# Shibobi_PowerMeasure.net
KiCad netlist of a schematic drawn in EAGLE
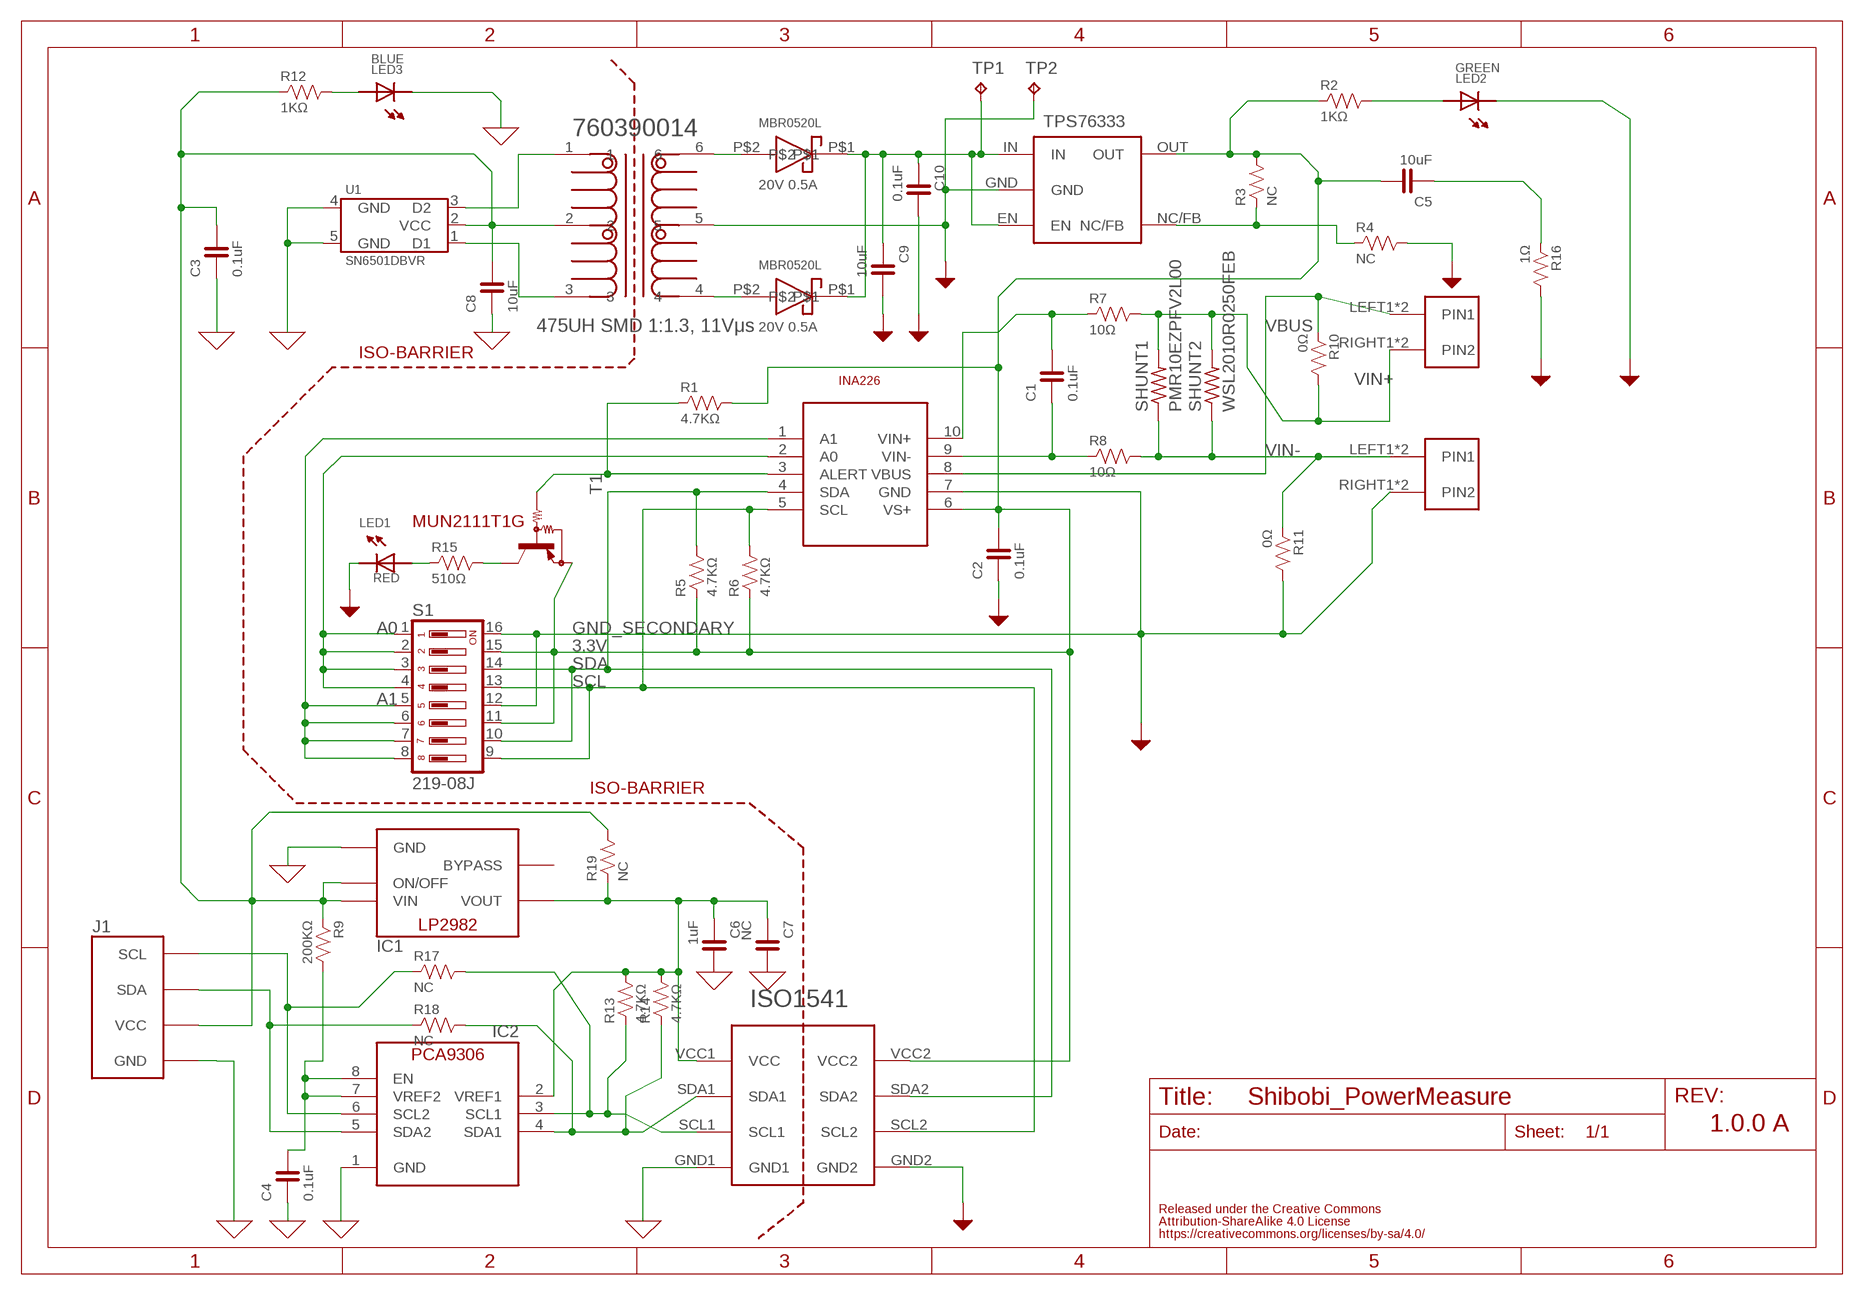
[diagram p0: schematic, sheet 1]

(export (version "E")
  (design (tool "Eeschema 10.0.6"))
  (components
    (comp (ref "C1")
      (value "0.1uF")
      (footprint "eagle-import:0603")
      (libsource (lib "eagle-import") (part "CAPACITOR-0603"))
    )
    (comp (ref "C2")
      (value "0.1uF")
      (footprint "eagle-import:0603")
      (libsource (lib "eagle-import") (part "CAPACITOR-0603"))
    )
    (comp (ref "C3")
      (value "0.1uF")
      (footprint "eagle-import:0603")
      (libsource (lib "eagle-import") (part "CAPACITOR-0603"))
    )
    (comp (ref "C4")
      (value "0.1uF")
      (footprint "eagle-import:0603")
      (libsource (lib "eagle-import") (part "CAPACITOR-0603"))
    )
    (comp (ref "C5")
      (value "10uF")
      (footprint "eagle-import:0603")
      (libsource (lib "eagle-import") (part "CAPACITOR-0603"))
    )
    (comp (ref "C6")
      (value "1uF")
      (footprint "eagle-import:0603")
      (libsource (lib "eagle-import") (part "CAPACITOR-0603"))
    )
    (comp (ref "C7")
      (value "NC")
      (footprint "eagle-import:0603")
      (libsource (lib "eagle-import") (part "CAPACITOR-0603"))
    )
    (comp (ref "C8")
      (value "10uF")
      (footprint "eagle-import:0603")
      (libsource (lib "eagle-import") (part "CAPACITOR-0603"))
    )
    (comp (ref "C9")
      (value "10uF")
      (footprint "eagle-import:0603")
      (libsource (lib "eagle-import") (part "CAPACITOR-0603"))
    )
    (comp (ref "C10")
      (value "0.1uF")
      (footprint "eagle-import:0603")
      (libsource (lib "eagle-import") (part "CAPACITOR-0603"))
    )
    (comp (ref "D1")
      (value "MBR0520L")
      (footprint "eagle-import:MBR0502L")
      (libsource (lib "eagle-import") (part "MBR0520L"))
    )
    (comp (ref "D2")
      (value "MBR0520L")
      (footprint "eagle-import:MBR0502L")
      (libsource (lib "eagle-import") (part "MBR0520L"))
    )
    (comp (ref "IC1")
      (value "3.3V")
      (footprint "eagle-import:SOT-23-5")
      (libsource (lib "eagle-import") (part "LP2982"))
    )
    (comp (ref "IC2")
      (value "PCA9306GM")
      (footprint "eagle-import:XQFN8")
      (libsource (lib "eagle-import") (part "PCA9306GM"))
    )
    (comp (ref "ISO")
      (value "ISO1541")
      (footprint "eagle-import:ISO1541")
      (libsource (lib "eagle-import") (part "ISO1541"))
    )
    (comp (ref "J1")
      (value "FABO_BRICK_I2C-S04B-PASK-2")
      (footprint "eagle-import:FABO_BRICK_I2C_S04B-PASK-2")
      (libsource (lib "eagle-import") (part "FABO_BRICK_I2C-S04B-PASK-2"))
    )
    (comp (ref "LED1")
      (value "RED")
      (footprint "eagle-import:0603")
      (libsource (lib "eagle-import") (part "LED-0603"))
    )
    (comp (ref "LED2")
      (value "GREEN")
      (footprint "eagle-import:0603")
      (libsource (lib "eagle-import") (part "LED-0603"))
    )
    (comp (ref "LED3")
      (value "BLUE")
      (footprint "eagle-import:0603")
      (libsource (lib "eagle-import") (part "LED-0603"))
    )
    (comp (ref "R1")
      (value "4.7KΩ")
      (footprint "eagle-import:0603")
      (libsource (lib "eagle-import") (part "RESISTOR-0603"))
    )
    (comp (ref "R2")
      (value "1KΩ")
      (footprint "eagle-import:0603")
      (libsource (lib "eagle-import") (part "RESISTOR-0603"))
    )
    (comp (ref "R3")
      (value "NC")
      (footprint "eagle-import:0603")
      (libsource (lib "eagle-import") (part "RESISTOR-0603"))
    )
    (comp (ref "R4")
      (value "NC")
      (footprint "eagle-import:0603")
      (libsource (lib "eagle-import") (part "RESISTOR-0603"))
    )
    (comp (ref "R5")
      (value "4.7KΩ")
      (footprint "eagle-import:0603")
      (libsource (lib "eagle-import") (part "RESISTOR-0603"))
    )
    (comp (ref "R6")
      (value "4.7KΩ")
      (footprint "eagle-import:0603")
      (libsource (lib "eagle-import") (part "RESISTOR-0603"))
    )
    (comp (ref "R7")
      (value "10Ω")
      (footprint "eagle-import:0603")
      (libsource (lib "eagle-import") (part "RESISTOR-0603"))
    )
    (comp (ref "R8")
      (value "10Ω")
      (footprint "eagle-import:0603")
      (libsource (lib "eagle-import") (part "RESISTOR-0603"))
    )
    (comp (ref "R9")
      (value "200KΩ")
      (footprint "eagle-import:0603")
      (libsource (lib "eagle-import") (part "RESISTOR-0603"))
    )
    (comp (ref "R10")
      (value "0Ω")
      (footprint "eagle-import:0603")
      (libsource (lib "eagle-import") (part "RESISTOR-0603"))
    )
    (comp (ref "R11")
      (value "0Ω")
      (footprint "eagle-import:0603")
      (libsource (lib "eagle-import") (part "RESISTOR-0603"))
    )
    (comp (ref "R12")
      (value "1KΩ")
      (footprint "eagle-import:0603")
      (libsource (lib "eagle-import") (part "RESISTOR-0603"))
    )
    (comp (ref "R13")
      (value "4.7KΩ")
      (footprint "eagle-import:0603")
      (libsource (lib "eagle-import") (part "RESISTOR-0603"))
    )
    (comp (ref "R14")
      (value "4.7KΩ")
      (footprint "eagle-import:0603")
      (libsource (lib "eagle-import") (part "RESISTOR-0603"))
    )
    (comp (ref "R15")
      (value "510Ω")
      (footprint "eagle-import:0603")
      (libsource (lib "eagle-import") (part "RESISTOR-0603"))
    )
    (comp (ref "R16")
      (value "1Ω")
      (footprint "eagle-import:0603")
      (libsource (lib "eagle-import") (part "RESISTOR-0603"))
    )
    (comp (ref "R17")
      (value "NC")
      (footprint "eagle-import:0603")
      (libsource (lib "eagle-import") (part "RESISTOR-0603"))
    )
    (comp (ref "R18")
      (value "NC")
      (footprint "eagle-import:0603")
      (libsource (lib "eagle-import") (part "RESISTOR-0603"))
    )
    (comp (ref "R19")
      (value "NC")
      (footprint "eagle-import:0603")
      (libsource (lib "eagle-import") (part "RESISTOR-0603"))
    )
    (comp (ref "S1")
      (value "219-08J")
      (footprint "eagle-import:CTS-219-08J")
      (libsource (lib "eagle-import") (part "219-08J"))
    )
    (comp (ref "SHUNT1")
      (value "PMR10EZPFV2L00")
      (footprint "eagle-import:PMR10EZPFV2L00")
      (libsource (lib "eagle-import") (part "PMR10EZPFV2L00"))
    )
    (comp (ref "SHUNT2")
      (value "WSL2010R0250FEB")
      (footprint "eagle-import:WSL2010R0250FEB")
      (libsource (lib "eagle-import") (part "WSL2010R0250FEB"))
    )
    (comp (ref "T1")
      (value "MUN2111T1-PNP_DRIVER-SC59-BEC")
      (footprint "eagle-import:SC59-BEC")
      (libsource (lib "eagle-import") (part "-PNP_DRIVER-SC59-BECMUN2111T1"))
    )
    (comp (ref "T2")
      (value "760390014")
      (footprint "eagle-import:760390014")
      (libsource (lib "eagle-import") (part "760390014"))
    )
    (comp (ref "TP1")
      (value "TPPAD1-17")
      (footprint "eagle-import:P1-17")
      (libsource (lib "eagle-import") (part "TPPAD1-17"))
    )
    (comp (ref "TP2")
      (value "TPPAD1-17")
      (footprint "eagle-import:P1-17")
      (libsource (lib "eagle-import") (part "TPPAD1-17"))
    )
    (comp (ref "U$2")
      (value "ML-1400-S1")
      (footprint "eagle-import:ML-1400-S1")
      (fields (field (name "SPICEPREFIX") "B"))
      (libsource (lib "eagle-import") (part "ML-1400-S1"))
    )
    (comp (ref "U$3")
      (value "ML-1400-S1")
      (footprint "eagle-import:ML-1400-S1")
      (libsource (lib "eagle-import") (part "ML-1400-S1"))
    )
    (comp (ref "U$8")
      (value "TPS76333")
      (footprint "eagle-import:TPS76333")
      (libsource (lib "eagle-import") (part "TPS76333"))
    )
    (comp (ref "U1")
      (value "SN6501DBVR")
      (footprint "eagle-import:SOT-23-5")
      (libsource (lib "eagle-import") (part "SN6501DBVR"))
    )
    (comp (ref "U2")
      (value "TI-INA226")
      (footprint "eagle-import:TI-INA226")
      (libsource (lib "eagle-import") (part "TI-INA226"))
    )
  )
  (nets
    (net (code "1") (name "/3.3V") (class "Default")
      (node (ref "C2") (pin "2") (pinfunction "2_2") (pintype "passive"))
      (node (ref "C5") (pin "2") (pinfunction "2_2") (pintype "passive"))
      (node (ref "ISO") (pin "VCC2") (pinfunction "VCC2_VCC2") (pintype "bidirectional"))
      (node (ref "R1") (pin "2") (pinfunction "2_2") (pintype "bidirectional"))
      (node (ref "R2") (pin "1") (pinfunction "1_1") (pintype "bidirectional"))
      (node (ref "R3") (pin "2") (pinfunction "2_2") (pintype "bidirectional"))
      (node (ref "R5") (pin "1") (pinfunction "1_1") (pintype "bidirectional"))
      (node (ref "R6") (pin "1") (pinfunction "1_1") (pintype "bidirectional"))
      (node (ref "S1") (pin "11") (pinfunction "11_11") (pintype "passive"))
      (node (ref "S1") (pin "15") (pinfunction "15_15") (pintype "passive"))
      (node (ref "T1") (pin "E") (pinfunction "E_E") (pintype "passive"))
      (node (ref "U$8") (pin "OUT") (pinfunction "OUT_OUT") (pintype "bidirectional"))
      (node (ref "U2") (pin "6") (pinfunction "VS+_6") (pintype "bidirectional"))
    )
    (net (code "2") (name "/A0") (class "Default")
      (node (ref "S1") (pin "1") (pinfunction "1_1") (pintype "passive"))
      (node (ref "S1") (pin "2") (pinfunction "2_2") (pintype "passive"))
      (node (ref "S1") (pin "3") (pinfunction "3_3") (pintype "passive"))
      (node (ref "S1") (pin "4") (pinfunction "4_4") (pintype "passive"))
      (node (ref "U2") (pin "2") (pinfunction "A0_2") (pintype "bidirectional"))
    )
    (net (code "3") (name "/A1") (class "Default")
      (node (ref "S1") (pin "5") (pinfunction "5_5") (pintype "passive"))
      (node (ref "S1") (pin "6") (pinfunction "6_6") (pintype "passive"))
      (node (ref "S1") (pin "7") (pinfunction "7_7") (pintype "passive"))
      (node (ref "S1") (pin "8") (pinfunction "8_8") (pintype "passive"))
      (node (ref "U2") (pin "1") (pinfunction "A1_1") (pintype "bidirectional"))
    )
    (net (code "4") (name "/SCL") (class "Default")
      (node (ref "ISO") (pin "SCL2") (pinfunction "SCL2_SCL2") (pintype "bidirectional"))
      (node (ref "R6") (pin "2") (pinfunction "2_2") (pintype "bidirectional"))
      (node (ref "S1") (pin "13") (pinfunction "13_13") (pintype "passive"))
      (node (ref "S1") (pin "9") (pinfunction "9_9") (pintype "passive"))
      (node (ref "U2") (pin "5") (pinfunction "SCL_5") (pintype "bidirectional"))
    )
    (net (code "5") (name "/SDA") (class "Default")
      (node (ref "ISO") (pin "SDA2") (pinfunction "SDA2_SDA2") (pintype "bidirectional"))
      (node (ref "R5") (pin "2") (pinfunction "2_2") (pintype "bidirectional"))
      (node (ref "S1") (pin "10") (pinfunction "10_10") (pintype "passive"))
      (node (ref "S1") (pin "14") (pinfunction "14_14") (pintype "passive"))
      (node (ref "U2") (pin "4") (pinfunction "SDA_4") (pintype "bidirectional"))
    )
    (net (code "6") (name "/VBUS") (class "Default")
      (node (ref "R10") (pin "1") (pinfunction "1_1") (pintype "bidirectional"))
      (node (ref "U$2") (pin "LEFT1") (pinfunction "PIN1_LEFT1") (pintype "bidirectional"))
      (node (ref "U$2") (pin "LEFT2") (pinfunction "PIN1_LEFT2") (pintype "bidirectional"))
      (node (ref "U2") (pin "8") (pinfunction "VBUS_8") (pintype "bidirectional"))
    )
    (net (code "7") (name "/VIN+") (class "Default")
      (node (ref "R10") (pin "2") (pinfunction "2_2") (pintype "bidirectional"))
      (node (ref "R7") (pin "2") (pinfunction "2_2") (pintype "bidirectional"))
      (node (ref "SHUNT1") (pin "P$2") (pinfunction "2_P$2") (pintype "passive"))
      (node (ref "SHUNT2") (pin "P$2") (pinfunction "2_P$2") (pintype "passive"))
      (node (ref "U$2") (pin "RIGHT1") (pinfunction "PIN2_RIGHT1") (pintype "bidirectional"))
      (node (ref "U$2") (pin "RIGHT2") (pinfunction "PIN2_RIGHT2") (pintype "bidirectional"))
    )
    (net (code "8") (name "/VIN-") (class "Default")
      (node (ref "R11") (pin "1") (pinfunction "1_1") (pintype "bidirectional"))
      (node (ref "R8") (pin "2") (pinfunction "2_2") (pintype "bidirectional"))
      (node (ref "SHUNT1") (pin "P$1") (pinfunction "1_P$1") (pintype "passive"))
      (node (ref "SHUNT2") (pin "P$1") (pinfunction "1_P$1") (pintype "passive"))
      (node (ref "U$3") (pin "LEFT1") (pinfunction "PIN1_LEFT1") (pintype "bidirectional"))
      (node (ref "U$3") (pin "LEFT2") (pinfunction "PIN1_LEFT2") (pintype "bidirectional"))
    )
    (net (code "9") (name "GND") (class "Default")
      (node (ref "C3") (pin "1") (pinfunction "1_1") (pintype "passive"))
      (node (ref "C4") (pin "1") (pinfunction "1_1") (pintype "passive"))
      (node (ref "C6") (pin "2") (pinfunction "2_2") (pintype "passive"))
      (node (ref "C7") (pin "2") (pinfunction "2_2") (pintype "passive"))
      (node (ref "C8") (pin "1") (pinfunction "1_1") (pintype "passive"))
      (node (ref "IC1") (pin "2") (pinfunction "GND_2") (pintype "power_in"))
      (node (ref "IC2") (pin "1") (pinfunction "GND_1") (pintype "bidirectional"))
      (node (ref "ISO") (pin "GND1") (pinfunction "GND1_GND1") (pintype "bidirectional"))
      (node (ref "J1") (pin "GND") (pinfunction "GND_GND") (pintype "bidirectional"))
      (node (ref "LED3") (pin "CATHODE") (pinfunction "CATHODE_CATHODE") (pintype "passive"))
      (node (ref "U1") (pin "4") (pinfunction "GND_4") (pintype "bidirectional"))
      (node (ref "U1") (pin "5") (pinfunction "GND_5") (pintype "bidirectional"))
    )
    (net (code "10") (name "GND_SEC") (class "Default")
      (node (ref "C10") (pin "2") (pinfunction "2_2") (pintype "passive"))
      (node (ref "C2") (pin "1") (pinfunction "1_1") (pintype "passive"))
      (node (ref "C9") (pin "2") (pinfunction "2_2") (pintype "passive"))
      (node (ref "ISO") (pin "GND2") (pinfunction "GND2_GND2") (pintype "bidirectional"))
      (node (ref "LED1") (pin "CATHODE") (pinfunction "CATHODE_CATHODE") (pintype "passive"))
      (node (ref "LED2") (pin "CATHODE") (pinfunction "CATHODE_CATHODE") (pintype "passive"))
      (node (ref "R11") (pin "2") (pinfunction "2_2") (pintype "bidirectional"))
      (node (ref "R16") (pin "2") (pinfunction "2_2") (pintype "bidirectional"))
      (node (ref "R4") (pin "2") (pinfunction "2_2") (pintype "bidirectional"))
      (node (ref "S1") (pin "12") (pinfunction "12_12") (pintype "passive"))
      (node (ref "S1") (pin "16") (pinfunction "16_16") (pintype "passive"))
      (node (ref "T2") (pin "5") (pinfunction "5_5") (pintype "bidirectional"))
      (node (ref "TP2") (pin "TP") (pinfunction "TP_TP") (pintype "input"))
      (node (ref "U$3") (pin "RIGHT1") (pinfunction "PIN2_RIGHT1") (pintype "bidirectional"))
      (node (ref "U$3") (pin "RIGHT2") (pinfunction "PIN2_RIGHT2") (pintype "bidirectional"))
      (node (ref "U$8") (pin "GND") (pinfunction "GND_GND") (pintype "bidirectional"))
      (node (ref "U2") (pin "7") (pinfunction "GND_7") (pintype "bidirectional"))
    )
    (net (code "11") (name "Net-(C5-Pad1)") (class "Default")
      (node (ref "C5") (pin "1") (pinfunction "1_1") (pintype "passive"))
      (node (ref "R16") (pin "1") (pinfunction "1_1") (pintype "bidirectional"))
    )
    (net (code "12") (name "Net-(D1-P$1)") (class "Default")
      (node (ref "D1") (pin "P$2") (pinfunction "P$1_P$2") (pintype "bidirectional"))
      (node (ref "T2") (pin "6") (pinfunction "6_6") (pintype "bidirectional"))
    )
    (net (code "13") (name "Net-(D1-P$2)") (class "Default")
      (node (ref "C10") (pin "1") (pinfunction "1_1") (pintype "passive"))
      (node (ref "C9") (pin "1") (pinfunction "1_1") (pintype "passive"))
      (node (ref "D1") (pin "P$1") (pinfunction "P$2_P$1") (pintype "bidirectional"))
      (node (ref "D2") (pin "P$1") (pinfunction "P$2_P$1") (pintype "bidirectional"))
      (node (ref "TP1") (pin "TP") (pinfunction "TP_TP") (pintype "input"))
      (node (ref "U$8") (pin "EN") (pinfunction "EN_EN") (pintype "bidirectional"))
      (node (ref "U$8") (pin "IN") (pinfunction "IN_IN") (pintype "bidirectional"))
    )
    (net (code "14") (name "Net-(D2-P$1)") (class "Default")
      (node (ref "D2") (pin "P$2") (pinfunction "P$1_P$2") (pintype "bidirectional"))
      (node (ref "T2") (pin "4") (pinfunction "4_4") (pintype "bidirectional"))
    )
    (net (code "15") (name "Net-(IC1-ON{slash}OFF)") (class "Default")
      (node (ref "C3") (pin "2") (pinfunction "2_2") (pintype "passive"))
      (node (ref "C8") (pin "2") (pinfunction "2_2") (pintype "passive"))
      (node (ref "IC1") (pin "1") (pinfunction "VIN_1") (pintype "input"))
      (node (ref "IC1") (pin "3") (pinfunction "ON/OFF_3") (pintype "input"))
      (node (ref "J1") (pin "VCC") (pinfunction "VCC_VCC") (pintype "bidirectional"))
      (node (ref "R12") (pin "1") (pinfunction "1_1") (pintype "bidirectional"))
      (node (ref "R19") (pin "2") (pinfunction "2_2") (pintype "bidirectional"))
      (node (ref "R9") (pin "1") (pinfunction "1_1") (pintype "bidirectional"))
      (node (ref "T2") (pin "2") (pinfunction "2_2") (pintype "bidirectional"))
      (node (ref "U1") (pin "2") (pinfunction "VCC_2") (pintype "bidirectional"))
    )
    (net (code "16") (name "Net-(IC1-VOUT)") (class "Default")
      (node (ref "C6") (pin "1") (pinfunction "1_1") (pintype "passive"))
      (node (ref "C7") (pin "1") (pinfunction "1_1") (pintype "passive"))
      (node (ref "IC1") (pin "5") (pinfunction "VOUT_5") (pintype "output"))
      (node (ref "IC2") (pin "2") (pinfunction "VREF1_2") (pintype "bidirectional"))
      (node (ref "ISO") (pin "VCC1") (pinfunction "VCC_VCC1") (pintype "bidirectional"))
      (node (ref "R13") (pin "2") (pinfunction "2_2") (pintype "bidirectional"))
      (node (ref "R14") (pin "2") (pinfunction "2_2") (pintype "bidirectional"))
      (node (ref "R19") (pin "1") (pinfunction "1_1") (pintype "bidirectional"))
    )
    (net (code "17") (name "Net-(IC2-EN)") (class "Default")
      (node (ref "C4") (pin "2") (pinfunction "2_2") (pintype "passive"))
      (node (ref "IC2") (pin "7") (pinfunction "VREF2_7") (pintype "bidirectional"))
      (node (ref "IC2") (pin "8") (pinfunction "EN_8") (pintype "bidirectional"))
      (node (ref "R9") (pin "2") (pinfunction "2_2") (pintype "bidirectional"))
    )
    (net (code "18") (name "Net-(IC2-SCL1)") (class "Default")
      (node (ref "IC2") (pin "3") (pinfunction "SCL1_3") (pintype "bidirectional"))
      (node (ref "ISO") (pin "SCL1") (pinfunction "SCL1_SCL1") (pintype "bidirectional"))
      (node (ref "R13") (pin "1") (pinfunction "1_1") (pintype "bidirectional"))
      (node (ref "R17") (pin "2") (pinfunction "2_2") (pintype "bidirectional"))
    )
    (net (code "19") (name "Net-(IC2-SCL2)") (class "Default")
      (node (ref "IC2") (pin "6") (pinfunction "SCL2_6") (pintype "bidirectional"))
      (node (ref "J1") (pin "SCL") (pinfunction "SCL_SCL") (pintype "bidirectional"))
      (node (ref "R17") (pin "1") (pinfunction "1_1") (pintype "bidirectional"))
    )
    (net (code "20") (name "Net-(IC2-SDA1)") (class "Default")
      (node (ref "IC2") (pin "4") (pinfunction "SDA1_4") (pintype "bidirectional"))
      (node (ref "ISO") (pin "SDA1") (pinfunction "SDA1_SDA1") (pintype "bidirectional"))
      (node (ref "R14") (pin "1") (pinfunction "1_1") (pintype "bidirectional"))
      (node (ref "R18") (pin "2") (pinfunction "2_2") (pintype "bidirectional"))
    )
    (net (code "21") (name "Net-(IC2-SDA2)") (class "Default")
      (node (ref "IC2") (pin "5") (pinfunction "SDA2_5") (pintype "bidirectional"))
      (node (ref "J1") (pin "SDA") (pinfunction "SDA_SDA") (pintype "bidirectional"))
      (node (ref "R18") (pin "1") (pinfunction "1_1") (pintype "bidirectional"))
    )
    (net (code "22") (name "Net-(LED1-PadANODE)") (class "Default")
      (node (ref "LED1") (pin "ANODE") (pinfunction "ANODE_ANODE") (pintype "passive"))
      (node (ref "R15") (pin "1") (pinfunction "1_1") (pintype "bidirectional"))
    )
    (net (code "23") (name "Net-(LED2-PadANODE)") (class "Default")
      (node (ref "LED2") (pin "ANODE") (pinfunction "ANODE_ANODE") (pintype "passive"))
      (node (ref "R2") (pin "2") (pinfunction "2_2") (pintype "bidirectional"))
    )
    (net (code "24") (name "Net-(LED3-PadANODE)") (class "Default")
      (node (ref "LED3") (pin "ANODE") (pinfunction "ANODE_ANODE") (pintype "passive"))
      (node (ref "R12") (pin "2") (pinfunction "2_2") (pintype "bidirectional"))
    )
    (net (code "25") (name "Net-(R3-Pad1)") (class "Default")
      (node (ref "R3") (pin "1") (pinfunction "1_1") (pintype "bidirectional"))
      (node (ref "R4") (pin "1") (pinfunction "1_1") (pintype "bidirectional"))
      (node (ref "U$8") (pin "NC/FB") (pinfunction "NC/FB_NC/FB") (pintype "bidirectional"))
    )
    (net (code "26") (name "Net-(R15-Pad2)") (class "Default")
      (node (ref "R15") (pin "2") (pinfunction "2_2") (pintype "bidirectional"))
      (node (ref "T1") (pin "C") (pinfunction "C_C") (pintype "passive"))
    )
    (net (code "27") (name "Net-(U1-D1)") (class "Default")
      (node (ref "T2") (pin "3") (pinfunction "3_3") (pintype "bidirectional"))
      (node (ref "U1") (pin "1") (pinfunction "D1_1") (pintype "bidirectional"))
    )
    (net (code "28") (name "Net-(U1-D2)") (class "Default")
      (node (ref "T2") (pin "1") (pinfunction "1_1") (pintype "bidirectional"))
      (node (ref "U1") (pin "3") (pinfunction "D2_3") (pintype "bidirectional"))
    )
    (net (code "29") (name "Net-(U2-ALERT)") (class "Default")
      (node (ref "R1") (pin "1") (pinfunction "1_1") (pintype "bidirectional"))
      (node (ref "T1") (pin "B") (pinfunction "B_B") (pintype "passive"))
      (node (ref "U2") (pin "3") (pinfunction "ALERT_3") (pintype "bidirectional"))
    )
    (net (code "30") (name "Net-(U2-VIN+)") (class "Default")
      (node (ref "C1") (pin "2") (pinfunction "2_2") (pintype "passive"))
      (node (ref "R7") (pin "1") (pinfunction "1_1") (pintype "bidirectional"))
      (node (ref "U2") (pin "10") (pinfunction "VIN+_10") (pintype "bidirectional"))
    )
    (net (code "31") (name "Net-(U2-VIN-)") (class "Default")
      (node (ref "C1") (pin "1") (pinfunction "1_1") (pintype "passive"))
      (node (ref "R8") (pin "1") (pinfunction "1_1") (pintype "bidirectional"))
      (node (ref "U2") (pin "9") (pinfunction "VIN-_9") (pintype "bidirectional"))
    )
    (net (code "32") (name "unconnected-(IC1-BYPASS-Pad4)") (class "Default")
      (node (ref "IC1") (pin "4") (pinfunction "BYPASS_4") (pintype "bidirectional"))
    )
  )
)
